# Ethernet.net
KiCad netlist of a schematic drawn in Altium Designer
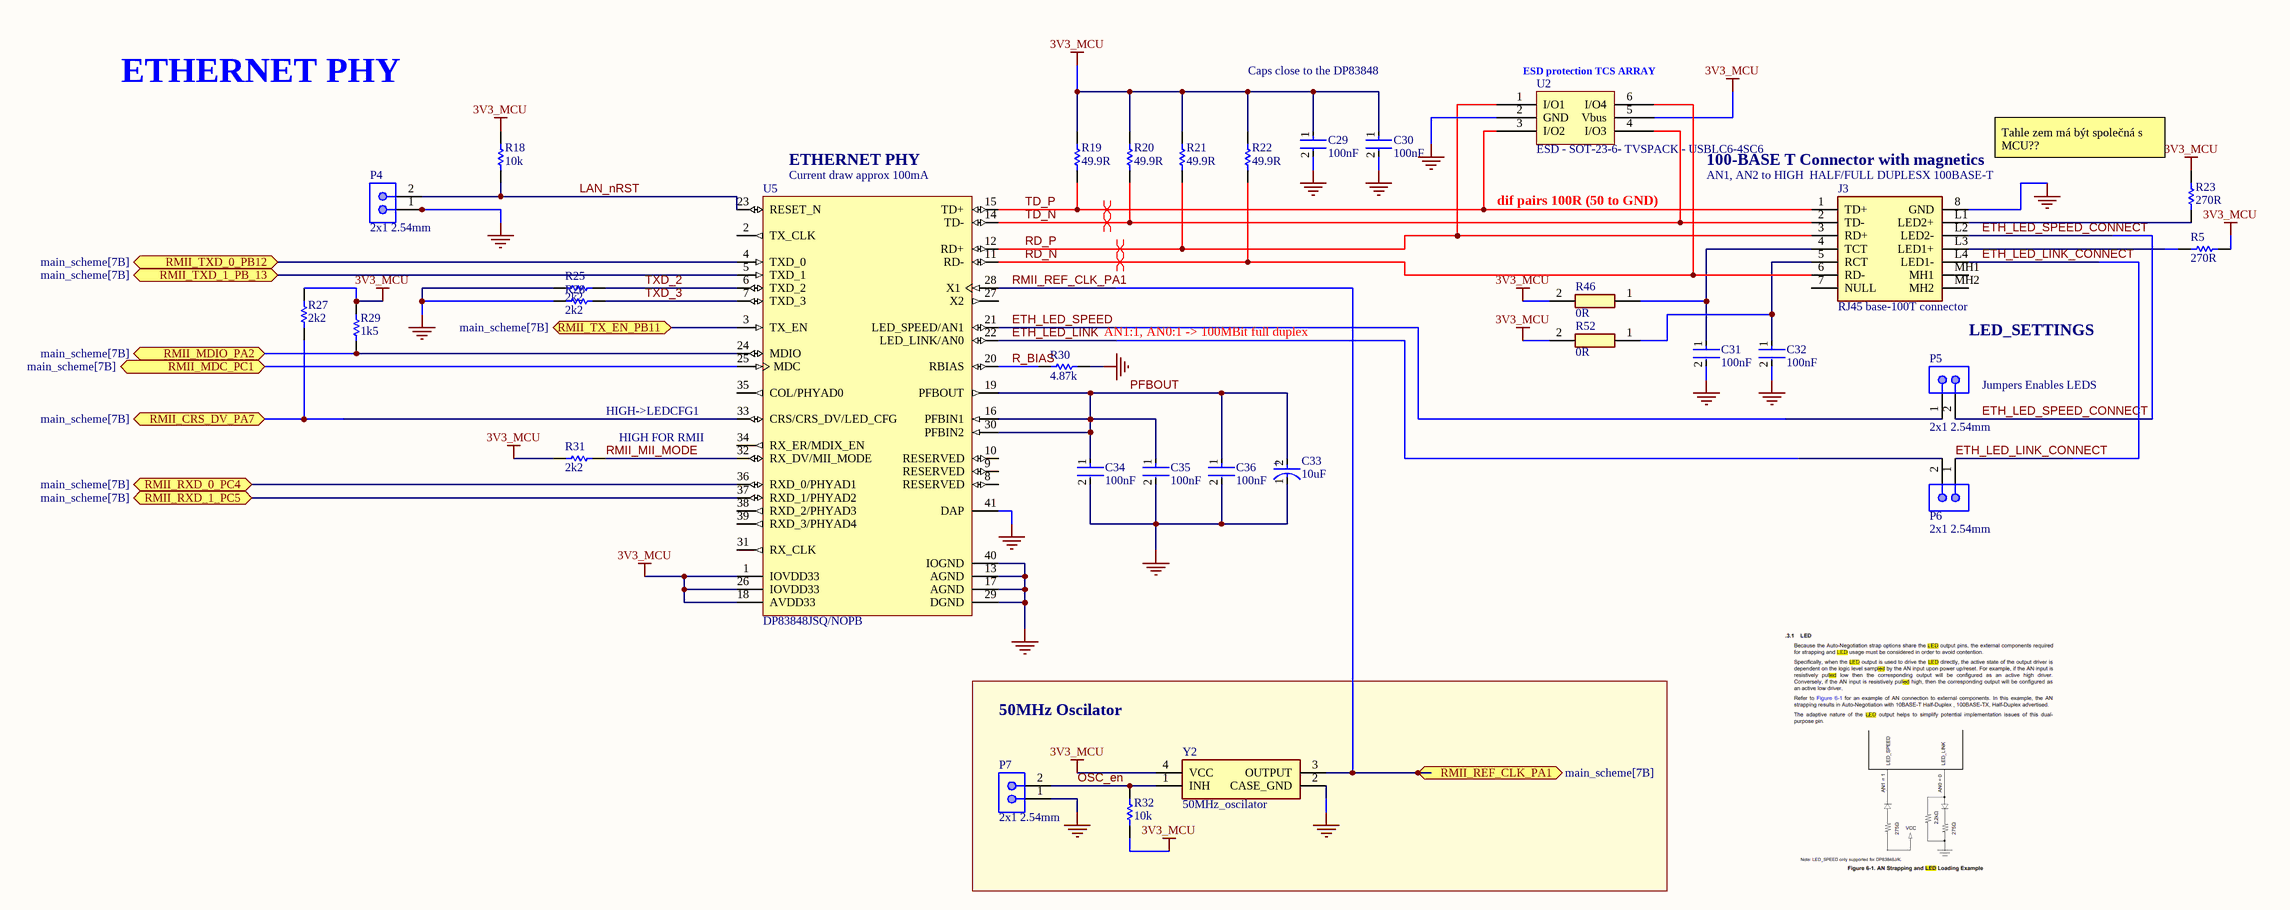
[diagram p0: Ethernet.SchDoc]

(export (version "E")
  (design (tool "Eeschema 10.0.6"))
  (components
    (comp (ref "C29")
      (value "100nF")
      (footprint "0402 CAP")
      (description "Cap Ceramic 0402,0.1uF, 25V,10%")
      (fields (field (name "PARTNUMBER") "C0402C104K3RACTU"))
      (libsource (lib "Schlib1") (part "CAP 0402 - 100nF"))
    )
    (comp (ref "C30")
      (value "100nF")
      (footprint "0402 CAP")
      (description "Cap Ceramic 0402,0.1uF, 25V,10%")
      (fields (field (name "PARTNUMBER") "C0402C104K3RACTU"))
      (libsource (lib "Schlib1") (part "CAP 0402 - 100nF"))
    )
    (comp (ref "C31")
      (value "100nF")
      (footprint "0402 CAP")
      (description "Cap Ceramic 0402,0.1uF, 25V,10%")
      (fields (field (name "PARTNUMBER") "C0402C104K3RACTU"))
      (libsource (lib "Schlib1") (part "CAP 0402 - 100nF"))
    )
    (comp (ref "C32")
      (value "100nF")
      (footprint "0402 CAP")
      (description "Cap Ceramic 0402,0.1uF, 25V,10%")
      (fields (field (name "PARTNUMBER") "C0402C104K3RACTU"))
      (libsource (lib "Schlib1") (part "CAP 0402 - 100nF"))
    )
    (comp (ref "C33")
      (value "10uF")
      (footprint "0603_tantal")
      (description "CAP TANT POLY 10UF 10V 0603 20%")
      (fields (field (name "PARTNUMBER") "F381A106MMAAH1"))
      (libsource (lib "Schlib1") (part "CAP 0603 Tantal -10uF"))
    )
    (comp (ref "C34")
      (value "100nF")
      (footprint "0402 CAP")
      (description "Cap Ceramic 0402,0.1uF, 25V,10%")
      (fields (field (name "PARTNUMBER") "C0402C104K3RACTU"))
      (libsource (lib "Schlib1") (part "CAP 0402 - 100nF"))
    )
    (comp (ref "C35")
      (value "100nF")
      (footprint "0402 CAP")
      (description "Cap Ceramic 0402,0.1uF, 25V,10%")
      (fields (field (name "PARTNUMBER") "C0402C104K3RACTU"))
      (libsource (lib "Schlib1") (part "CAP 0402 - 100nF"))
    )
    (comp (ref "C36")
      (value "100nF")
      (footprint "0402 CAP")
      (description "Cap Ceramic 0402,0.1uF, 25V,10%")
      (fields (field (name "PARTNUMBER") "C0402C104K3RACTU"))
      (libsource (lib "Schlib1") (part "CAP 0402 - 100nF"))
    )
    (comp (ref "J3")
      (value "RJ45 base-100T connector")
      (footprint "ARJM11D7009ABEW2 - better3D")
      (description "Connector RJ45 base-100T CAT5/6, with magnetics inside")
      (fields (field (name "PARTNUMBER") "ARJM11D7-009-AB-EW2"))
      (libsource (lib "Schlib1") (part "RJ45 base-100T connector"))
    )
    (comp (ref "P4")
      (value "2x1 2.54mm")
      (footprint "2.54mm header 2x1")
      (fields (field (name "PARTNUMBER") "5-146280-2"))
      (libsource (lib "Schlib1") (part "Header - 2x1 2.54mm"))
    )
    (comp (ref "P5")
      (value "2x1 2.54mm")
      (footprint "2.54mm header 2x1")
      (fields (field (name "PARTNUMBER") "5-146280-2"))
      (libsource (lib "") (part "Header - 2x1 2.54mm_2"))
    )
    (comp (ref "P6")
      (value "2x1 2.54mm")
      (footprint "2.54mm header 2x1")
      (fields (field (name "PARTNUMBER") "5-146280-2"))
      (libsource (lib "") (part "Header - 2x1 2.54mm_1"))
    )
    (comp (ref "P7")
      (value "2x1 2.54mm")
      (footprint "2.54mm header 2x1")
      (fields (field (name "PARTNUMBER") "5-146280-2"))
      (libsource (lib "Schlib1") (part "Header - 2x1 2.54mm"))
    )
    (comp (ref "R5")
      (value "270R")
      (footprint "RESC1005X40X25NL05T05")
      (description "Resistor - 0402 - 270R - 1% - 125mW")
      (fields (field (name "PARTNUMBER") "CRGP0402F270R"))
      (libsource (lib "Schlib1") (part "Resistor - 0402 -270R"))
    )
    (comp (ref "R18")
      (value "10k")
      (footprint "RESC1005X40X25NL05T05")
      (description "Resistor - 0402 -  10k - 5% - 125mW")
      (fields (field (name "PARTNUMBER") "RC0402JR-7W10KL"))
      (libsource (lib "Schlib1") (part "Resistor - 0402 -10k"))
    )
    (comp (ref "R19")
      (value "49.9R")
      (footprint "RESC1005X40X25NL05T05")
      (description "Resistor - 0402 -  49.9R - 1% - 100mW")
      (fields (field (name "PARTNUMBER") "ERJ-2RKF49R9X"))
      (libsource (lib "Schlib1") (part "Resistor - 0402 - 49.9R"))
    )
    (comp (ref "R20")
      (value "49.9R")
      (footprint "RESC1005X40X25NL05T05")
      (description "Resistor - 0402 -  49.9R - 1% - 100mW")
      (fields (field (name "PARTNUMBER") "ERJ-2RKF49R9X"))
      (libsource (lib "Schlib1") (part "Resistor - 0402 - 49.9R"))
    )
    (comp (ref "R21")
      (value "49.9R")
      (footprint "RESC1005X40X25NL05T05")
      (description "Resistor - 0402 -  49.9R - 1% - 100mW")
      (fields (field (name "PARTNUMBER") "ERJ-2RKF49R9X"))
      (libsource (lib "Schlib1") (part "Resistor - 0402 - 49.9R"))
    )
    (comp (ref "R22")
      (value "49.9R")
      (footprint "RESC1005X40X25NL05T05")
      (description "Resistor - 0402 -  49.9R - 1% - 100mW")
      (fields (field (name "PARTNUMBER") "ERJ-2RKF49R9X"))
      (libsource (lib "Schlib1") (part "Resistor - 0402 - 49.9R"))
    )
    (comp (ref "R23")
      (value "270R")
      (footprint "RESC1005X40X25NL05T05")
      (description "Resistor - 0402 - 270R - 1% - 125mW")
      (fields (field (name "PARTNUMBER") "CRGP0402F270R"))
      (libsource (lib "Schlib1") (part "Resistor - 0402 -270R"))
    )
    (comp (ref "R25")
      (value "2k2")
      (footprint "RESC1005X40X25NL05T05")
      (description "Resistor - 0402 - 2k2 - 1% - 200mW")
      (fields (field (name "PARTNUMBER") "ERJ-PA2F2201X"))
      (libsource (lib "Schlib1") (part "Resistor - 0402 - 2k2"))
    )
    (comp (ref "R27")
      (value "2k2")
      (footprint "RESC1005X40X25NL05T05")
      (description "Resistor - 0402 - 2k2 - 1% - 200mW")
      (fields (field (name "PARTNUMBER") "ERJ-PA2F2201X"))
      (libsource (lib "Schlib1") (part "Resistor - 0402 - 2k2"))
    )
    (comp (ref "R28")
      (value "2k2")
      (footprint "RESC1005X40X25NL05T05")
      (description "Resistor - 0402 - 2k2 - 1% - 200mW")
      (fields (field (name "PARTNUMBER") "ERJ-PA2F2201X"))
      (libsource (lib "Schlib1") (part "Resistor - 0402 - 2k2"))
    )
    (comp (ref "R29")
      (value "1k5")
      (footprint "RESC1005X40X25NL05T05")
      (description "Resistor - 0402 - 1k5 - 1% - 100mW")
      (fields (field (name "PARTNUMBER") "ERJ2RKF6800X"))
      (libsource (lib "Schlib1") (part "Resistor - 0402 - 1k5"))
    )
    (comp (ref "R30")
      (value "4.87k")
      (footprint "RESC1005X40X25NL05T05")
      (description "Resistor - 0402 -  4.87k - 1% - 100mW")
      (fields (field (name "PARTNUMBER") "ERJ-2RKF4871X"))
      (libsource (lib "Schlib1") (part "Resistor - 0402 - 4.87k"))
    )
    (comp (ref "R31")
      (value "2k2")
      (footprint "RESC1005X40X25NL05T05")
      (description "Resistor - 0402 - 2k2 - 1% - 200mW")
      (fields (field (name "PARTNUMBER") "ERJ-PA2F2201X"))
      (libsource (lib "Schlib1") (part "Resistor - 0402 - 2k2"))
    )
    (comp (ref "R32")
      (value "10k")
      (footprint "RESC1005X40X25NL05T05")
      (description "Resistor - 0402 -  10k - 5% - 125mW")
      (fields (field (name "PARTNUMBER") "RC0402JR-7W10KL"))
      (libsource (lib "Schlib1") (part "Resistor - 0402 -10k"))
    )
    (comp (ref "R46")
      (value "0R")
      (footprint "PcbLib1:0603- SMD resistor")
      (description "Resistor 0603 0R")
      (fields (field (name "PARTNUMBER") "ERJ-3GEY0R00V"))
      (libsource (lib "Schlib1") (part "RESISTOR - 0603 - 0R"))
    )
    (comp (ref "R52")
      (value "0R")
      (footprint "PcbLib1:0603- SMD resistor")
      (description "Resistor 0603 0R")
      (fields (field (name "PARTNUMBER") "ERJ-3GEY0R00V"))
      (libsource (lib "Schlib1") (part "RESISTOR - 0603 - 0R"))
    )
    (comp (ref "U2")
      (value "ESD - SOT-23-6- TVSPACK - USBLC6-4SC6")
      (footprint "SOT95P280X145-6N")
      (description "ESD Suppressors / TVS Diodes Low Cap ESD Protect -  Working VOltage 5.25V, Br: 6V, Clamp 17V")
      (fields (field (name "PARTNUMBER") "USBLC6-4SC6"))
      (libsource (lib "Schlib1") (part "ESD - SOT-23-6- TVSPACK - USBLC6-4SC6"))
    )
    (comp (ref "U5")
      (value "DP83848JSQ/NOPB")
      (footprint "RTA0040A_V")
      (libsource (lib "Schlib1") (part "LAN-DP83848JSQ/NOPB"))
    )
    (comp (ref "Y2")
      (value "50MHz_oscilator")
      (footprint "PcbLib1:KC2016Z500000C15XXK")
      (description "Oscilator - 50MHz - 30ppm - 15pF - 1.71 - 3.63V")
      (fields (field (name "PARTNUMBER") "KC2016Z50.0000C15XXK"))
      (libsource (lib "Schlib1") (part "50MHz_oscilator"))
    )
  )
  (nets
    (net (code "1") (name "/ETH_LED_LINK") (class "Default")
      (node (ref "P6") (pin "2") (pinfunction "2_2") (pintype "passive"))
      (node (ref "U5") (pin "22") (pinfunction "LED_LINK/AN0_22") (pintype "bidirectional"))
    )
    (net (code "2") (name "/ETH_LED_LINK_CONNECT") (class "Default")
      (node (ref "J3") (pin "L4") (pinfunction "LED1-_L4") (pintype "passive"))
      (node (ref "P6") (pin "1") (pinfunction "1_1") (pintype "passive"))
    )
    (net (code "3") (name "/ETH_LED_SPEED") (class "Default")
      (node (ref "P5") (pin "1") (pinfunction "1_1") (pintype "passive"))
      (node (ref "U5") (pin "21") (pinfunction "LED_SPEED/AN1_21") (pintype "bidirectional"))
    )
    (net (code "4") (name "/ETH_LED_SPEED_CONNECT") (class "Default")
      (node (ref "J3") (pin "L2") (pinfunction "LED2-_L2") (pintype "passive"))
      (node (ref "P5") (pin "2") (pinfunction "2_2") (pintype "passive"))
    )
    (net (code "5") (name "/LAN_nRST") (class "Default")
      (node (ref "P4") (pin "2") (pinfunction "2_2") (pintype "passive"))
      (node (ref "R18") (pin "2") (pinfunction "2_2") (pintype "passive"))
      (node (ref "U5") (pin "23") (pinfunction "RESET_N_23") (pintype "bidirectional"))
    )
    (net (code "6") (name "/OSC_en") (class "Default")
      (node (ref "P7") (pin "2") (pinfunction "2_2") (pintype "passive"))
      (node (ref "R32") (pin "1") (pinfunction "1_1") (pintype "passive"))
      (node (ref "Y2") (pin "1") (pinfunction "INH_1") (pintype "passive"))
    )
    (net (code "7") (name "/PFBOUT") (class "Default")
      (node (ref "C33") (pin "2") (pinfunction "A_2") (pintype "passive"))
      (node (ref "C34") (pin "1") (pinfunction "1_1") (pintype "passive"))
      (node (ref "C35") (pin "1") (pinfunction "1_1") (pintype "passive"))
      (node (ref "C36") (pin "1") (pinfunction "1_1") (pintype "passive"))
      (node (ref "U5") (pin "16") (pinfunction "PFBIN1_16") (pintype "input"))
      (node (ref "U5") (pin "19") (pinfunction "PFBOUT_19") (pintype "output"))
      (node (ref "U5") (pin "30") (pinfunction "PFBIN2_30") (pintype "input"))
    )
    (net (code "8") (name "/RD_N") (class "Default")
      (node (ref "J3") (pin "6") (pinfunction "RD-_6") (pintype "passive"))
      (node (ref "R22") (pin "2") (pinfunction "2_2") (pintype "passive"))
      (node (ref "U2") (pin "6") (pinfunction "I/O4_6") (pintype "passive"))
      (node (ref "U5") (pin "11") (pinfunction "RD-_11") (pintype "bidirectional"))
    )
    (net (code "9") (name "/RD_P") (class "Default")
      (node (ref "J3") (pin "3") (pinfunction "RD+_3") (pintype "passive"))
      (node (ref "R21") (pin "2") (pinfunction "2_2") (pintype "passive"))
      (node (ref "U2") (pin "1") (pinfunction "I/O1_1") (pintype "passive"))
      (node (ref "U5") (pin "12") (pinfunction "RD+_12") (pintype "bidirectional"))
    )
    (net (code "10") (name "/RMII_CRS_DV_PA7") (class "Default")
      (node (ref "R27") (pin "2") (pinfunction "2_2") (pintype "passive"))
      (node (ref "U5") (pin "33") (pinfunction "CRS/CRS_DV/LED_CFG_33") (pintype "bidirectional"))
    )
    (net (code "11") (name "/RMII_MDC_PC1") (class "Default")
      (node (ref "U5") (pin "25") (pinfunction "MDC_25") (pintype "input"))
    )
    (net (code "12") (name "/RMII_MDIO_PA2") (class "Default")
      (node (ref "R29") (pin "2") (pinfunction "2_2") (pintype "passive"))
      (node (ref "U5") (pin "24") (pinfunction "MDIO_24") (pintype "bidirectional"))
    )
    (net (code "13") (name "/RMII_MII_MODE") (class "Default")
      (node (ref "R31") (pin "2") (pinfunction "2_2") (pintype "passive"))
      (node (ref "U5") (pin "32") (pinfunction "RX_DV/MII_MODE_32") (pintype "bidirectional"))
    )
    (net (code "14") (name "/RMII_REF_CLK_PA1") (class "Default")
      (node (ref "U5") (pin "28") (pinfunction "X1_28") (pintype "input"))
      (node (ref "Y2") (pin "3") (pinfunction "OUTPUT_3") (pintype "passive"))
    )
    (net (code "15") (name "/RMII_RXD_0_PC4") (class "Default")
      (node (ref "U5") (pin "36") (pinfunction "RXD_0/PHYAD1_36") (pintype "bidirectional"))
    )
    (net (code "16") (name "/RMII_RXD_1_PC5") (class "Default")
      (node (ref "U5") (pin "37") (pinfunction "RXD_1/PHYAD2_37") (pintype "bidirectional"))
    )
    (net (code "17") (name "/RMII_TXD_0_PB12") (class "Default")
      (node (ref "U5") (pin "4") (pinfunction "TXD_0_4") (pintype "input"))
    )
    (net (code "18") (name "/RMII_TXD_1_PB_13") (class "Default")
      (node (ref "U5") (pin "5") (pinfunction "TXD_1_5") (pintype "input"))
    )
    (net (code "19") (name "/RMII_TX_EN_PB11") (class "Default")
      (node (ref "U5") (pin "3") (pinfunction "TX_EN_3") (pintype "input"))
    )
    (net (code "20") (name "/R_BIAS") (class "Default")
      (node (ref "R30") (pin "2") (pinfunction "2_2") (pintype "passive"))
      (node (ref "U5") (pin "20") (pinfunction "RBIAS_20") (pintype "bidirectional"))
    )
    (net (code "21") (name "/TD_N") (class "Default")
      (node (ref "J3") (pin "2") (pinfunction "TD-_2") (pintype "passive"))
      (node (ref "R20") (pin "2") (pinfunction "2_2") (pintype "passive"))
      (node (ref "U2") (pin "4") (pinfunction "I/O3_4") (pintype "passive"))
      (node (ref "U5") (pin "14") (pinfunction "TD-_14") (pintype "bidirectional"))
    )
    (net (code "22") (name "/TD_P") (class "Default")
      (node (ref "J3") (pin "1") (pinfunction "TD+_1") (pintype "passive"))
      (node (ref "R19") (pin "2") (pinfunction "2_2") (pintype "passive"))
      (node (ref "U2") (pin "3") (pinfunction "I/O2_3") (pintype "passive"))
      (node (ref "U5") (pin "15") (pinfunction "TD+_15") (pintype "bidirectional"))
    )
    (net (code "23") (name "/TXD_2") (class "Default")
      (node (ref "R25") (pin "1") (pinfunction "1_1") (pintype "passive"))
      (node (ref "U5") (pin "6") (pinfunction "TXD_2_6") (pintype "bidirectional"))
    )
    (net (code "24") (name "/TXD_3") (class "Default")
      (node (ref "R28") (pin "1") (pinfunction "1_1") (pintype "passive"))
      (node (ref "U5") (pin "7") (pinfunction "TXD_3_7") (pintype "bidirectional"))
    )
    (net (code "25") (name "3V3_MCU") (class "Default")
      (node (ref "C29") (pin "1") (pinfunction "1_1") (pintype "passive"))
      (node (ref "C30") (pin "1") (pinfunction "1_1") (pintype "passive"))
      (node (ref "R18") (pin "1") (pinfunction "1_1") (pintype "passive"))
      (node (ref "R19") (pin "1") (pinfunction "1_1") (pintype "passive"))
      (node (ref "R20") (pin "1") (pinfunction "1_1") (pintype "passive"))
      (node (ref "R21") (pin "1") (pinfunction "1_1") (pintype "passive"))
      (node (ref "R22") (pin "1") (pinfunction "1_1") (pintype "passive"))
      (node (ref "R23") (pin "1") (pinfunction "1_1") (pintype "passive"))
      (node (ref "R27") (pin "1") (pinfunction "1_1") (pintype "passive"))
      (node (ref "R29") (pin "1") (pinfunction "1_1") (pintype "passive"))
      (node (ref "R31") (pin "1") (pinfunction "1_1") (pintype "passive"))
      (node (ref "R32") (pin "2") (pinfunction "2_2") (pintype "passive"))
      (node (ref "R46") (pin "2") (pinfunction "2_2") (pintype "passive"))
      (node (ref "R5") (pin "1") (pinfunction "1_1") (pintype "passive"))
      (node (ref "R52") (pin "2") (pinfunction "2_2") (pintype "passive"))
      (node (ref "U2") (pin "5") (pinfunction "Vbus_5") (pintype "passive"))
      (node (ref "U5") (pin "1") (pinfunction "IOVDD33_1") (pintype "power_in"))
      (node (ref "U5") (pin "18") (pinfunction "AVDD33_18") (pintype "power_in"))
      (node (ref "U5") (pin "26") (pinfunction "IOVDD33_26") (pintype "power_in"))
      (node (ref "Y2") (pin "4") (pinfunction "VCC_4") (pintype "passive"))
    )
    (net (code "26") (name "GND") (class "Default")
      (node (ref "C29") (pin "2") (pinfunction "2_2") (pintype "passive"))
      (node (ref "C30") (pin "2") (pinfunction "2_2") (pintype "passive"))
      (node (ref "C31") (pin "2") (pinfunction "2_2") (pintype "passive"))
      (node (ref "C32") (pin "2") (pinfunction "2_2") (pintype "passive"))
      (node (ref "C33") (pin "1") (pinfunction "C_1") (pintype "passive"))
      (node (ref "C34") (pin "2") (pinfunction "2_2") (pintype "passive"))
      (node (ref "C35") (pin "2") (pinfunction "2_2") (pintype "passive"))
      (node (ref "C36") (pin "2") (pinfunction "2_2") (pintype "passive"))
      (node (ref "J3") (pin "8") (pinfunction "GND_8") (pintype "passive"))
      (node (ref "P4") (pin "1") (pinfunction "1_1") (pintype "passive"))
      (node (ref "P7") (pin "1") (pinfunction "1_1") (pintype "passive"))
      (node (ref "R25") (pin "2") (pinfunction "2_2") (pintype "passive"))
      (node (ref "R28") (pin "2") (pinfunction "2_2") (pintype "passive"))
      (node (ref "R30") (pin "1") (pinfunction "1_1") (pintype "passive"))
      (node (ref "U2") (pin "2") (pinfunction "GND_2") (pintype "passive"))
      (node (ref "U5") (pin "13") (pinfunction "AGND_13") (pintype "power_in"))
      (node (ref "U5") (pin "17") (pinfunction "AGND_17") (pintype "power_in"))
      (node (ref "U5") (pin "29") (pinfunction "DGND_29") (pintype "power_in"))
      (node (ref "U5") (pin "40") (pinfunction "IOGND_40") (pintype "power_in"))
      (node (ref "U5") (pin "41") (pinfunction "DAP_41") (pintype "passive"))
      (node (ref "Y2") (pin "2") (pinfunction "CASE_GND_2") (pintype "passive"))
    )
    (net (code "27") (name "Net-(J3-LED1+)") (class "Default")
      (node (ref "J3") (pin "L3") (pinfunction "LED1+_L3") (pintype "passive"))
      (node (ref "R5") (pin "2") (pinfunction "2_2") (pintype "passive"))
    )
    (net (code "28") (name "Net-(J3-LED2+)") (class "Default")
      (node (ref "J3") (pin "L1") (pinfunction "LED2+_L1") (pintype "passive"))
      (node (ref "R23") (pin "2") (pinfunction "2_2") (pintype "passive"))
    )
    (net (code "29") (name "Net-(J3-RCT)") (class "Default")
      (node (ref "C32") (pin "1") (pinfunction "1_1") (pintype "passive"))
      (node (ref "J3") (pin "5") (pinfunction "RCT_5") (pintype "passive"))
      (node (ref "R52") (pin "1") (pinfunction "1_1") (pintype "passive"))
    )
    (net (code "30") (name "Net-(J3-TCT)") (class "Default")
      (node (ref "C31") (pin "1") (pinfunction "1_1") (pintype "passive"))
      (node (ref "J3") (pin "4") (pinfunction "TCT_4") (pintype "passive"))
      (node (ref "R46") (pin "1") (pinfunction "1_1") (pintype "passive"))
    )
    (net (code "31") (name "unconnected-(J3-NULL-Pad7)") (class "Default")
      (node (ref "J3") (pin "7") (pinfunction "NULL_7") (pintype "passive"))
    )
    (net (code "32") (name "unconnected-(J3-PadMH1)") (class "Default")
      (node (ref "J3") (pin "MH1") (pinfunction "MH1_MH1") (pintype "passive"))
    )
    (net (code "33") (name "unconnected-(J3-PadMH2)") (class "Default")
      (node (ref "J3") (pin "MH2") (pinfunction "MH2_MH2") (pintype "passive"))
    )
    (net (code "34") (name "unconnected-(U5-COL{slash}PHYAD0-Pad35)") (class "Default")
      (node (ref "U5") (pin "35") (pinfunction "COL/PHYAD0_35") (pintype "output"))
    )
    (net (code "35") (name "unconnected-(U5-RESERVED-Pad8)") (class "Default")
      (node (ref "U5") (pin "8") (pinfunction "RESERVED_8") (pintype "bidirectional"))
    )
    (net (code "36") (name "unconnected-(U5-RESERVED-Pad9)") (class "Default")
      (node (ref "U5") (pin "9") (pinfunction "RESERVED_9") (pintype "bidirectional"))
    )
    (net (code "37") (name "unconnected-(U5-RESERVED-Pad10)") (class "Default")
      (node (ref "U5") (pin "10") (pinfunction "RESERVED_10") (pintype "bidirectional"))
    )
    (net (code "38") (name "unconnected-(U5-RXD_2{slash}PHYAD3-Pad38)") (class "Default")
      (node (ref "U5") (pin "38") (pinfunction "RXD_2/PHYAD3_38") (pintype "output"))
    )
    (net (code "39") (name "unconnected-(U5-RXD_3{slash}PHYAD4-Pad39)") (class "Default")
      (node (ref "U5") (pin "39") (pinfunction "RXD_3/PHYAD4_39") (pintype "output"))
    )
    (net (code "40") (name "unconnected-(U5-RX_CLK-Pad31)") (class "Default")
      (node (ref "U5") (pin "31") (pinfunction "RX_CLK_31") (pintype "output"))
    )
    (net (code "41") (name "unconnected-(U5-RX_ER{slash}MDIX_EN-Pad34)") (class "Default")
      (node (ref "U5") (pin "34") (pinfunction "RX_ER/MDIX_EN_34") (pintype "output"))
    )
    (net (code "42") (name "unconnected-(U5-TX_CLK-Pad2)") (class "Default")
      (node (ref "U5") (pin "2") (pinfunction "TX_CLK_2") (pintype "output"))
    )
    (net (code "43") (name "unconnected-(U5-X2-Pad27)") (class "Default")
      (node (ref "U5") (pin "27") (pinfunction "X2_27") (pintype "output"))
    )
  )
)
